# LED-zero35-SHIM.net
KiCad netlist of a schematic drawn in EAGLE
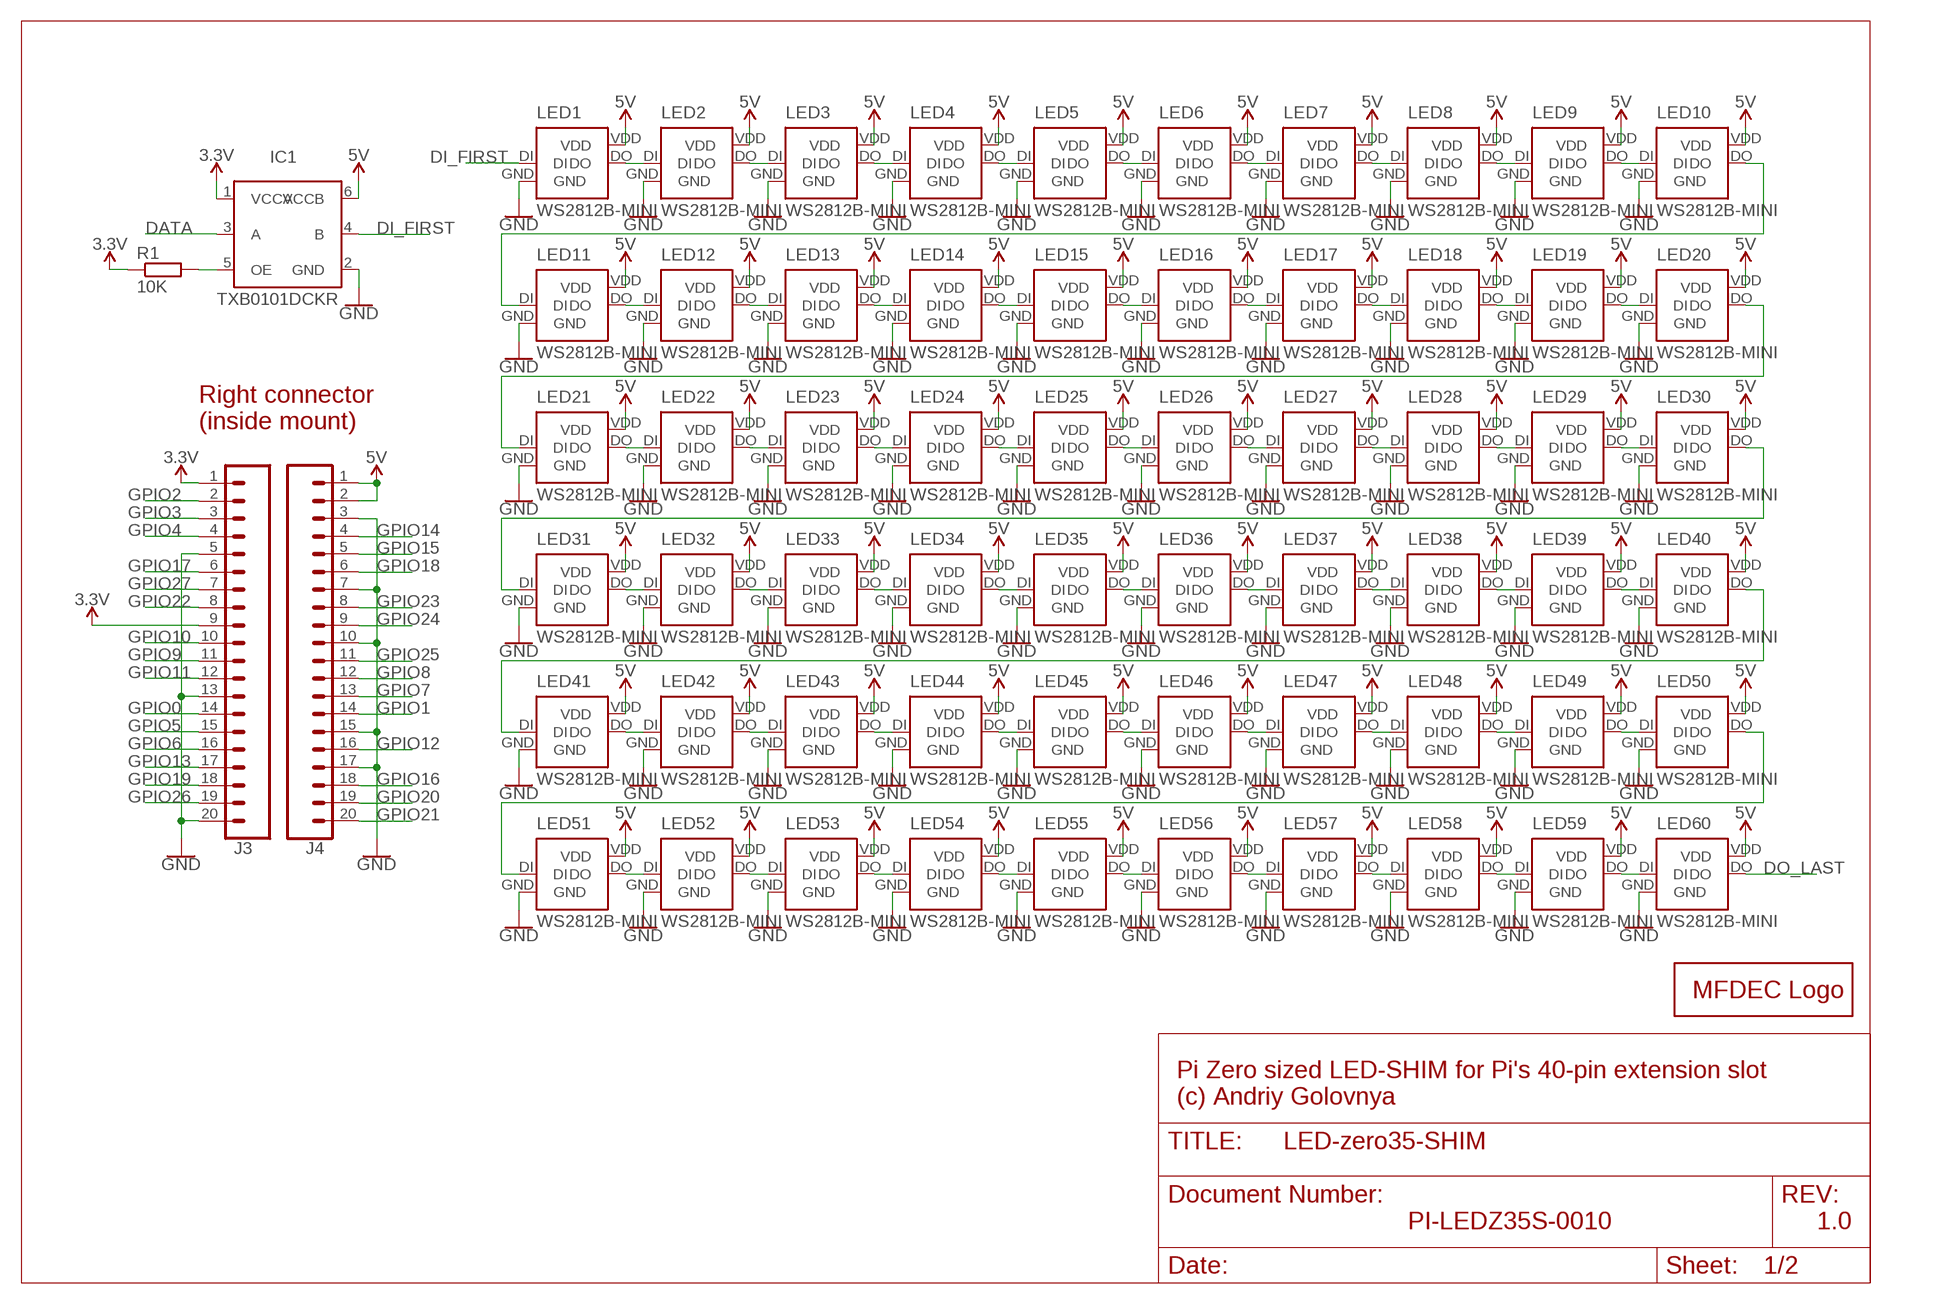
[diagram p0: schematic, sheet 1]
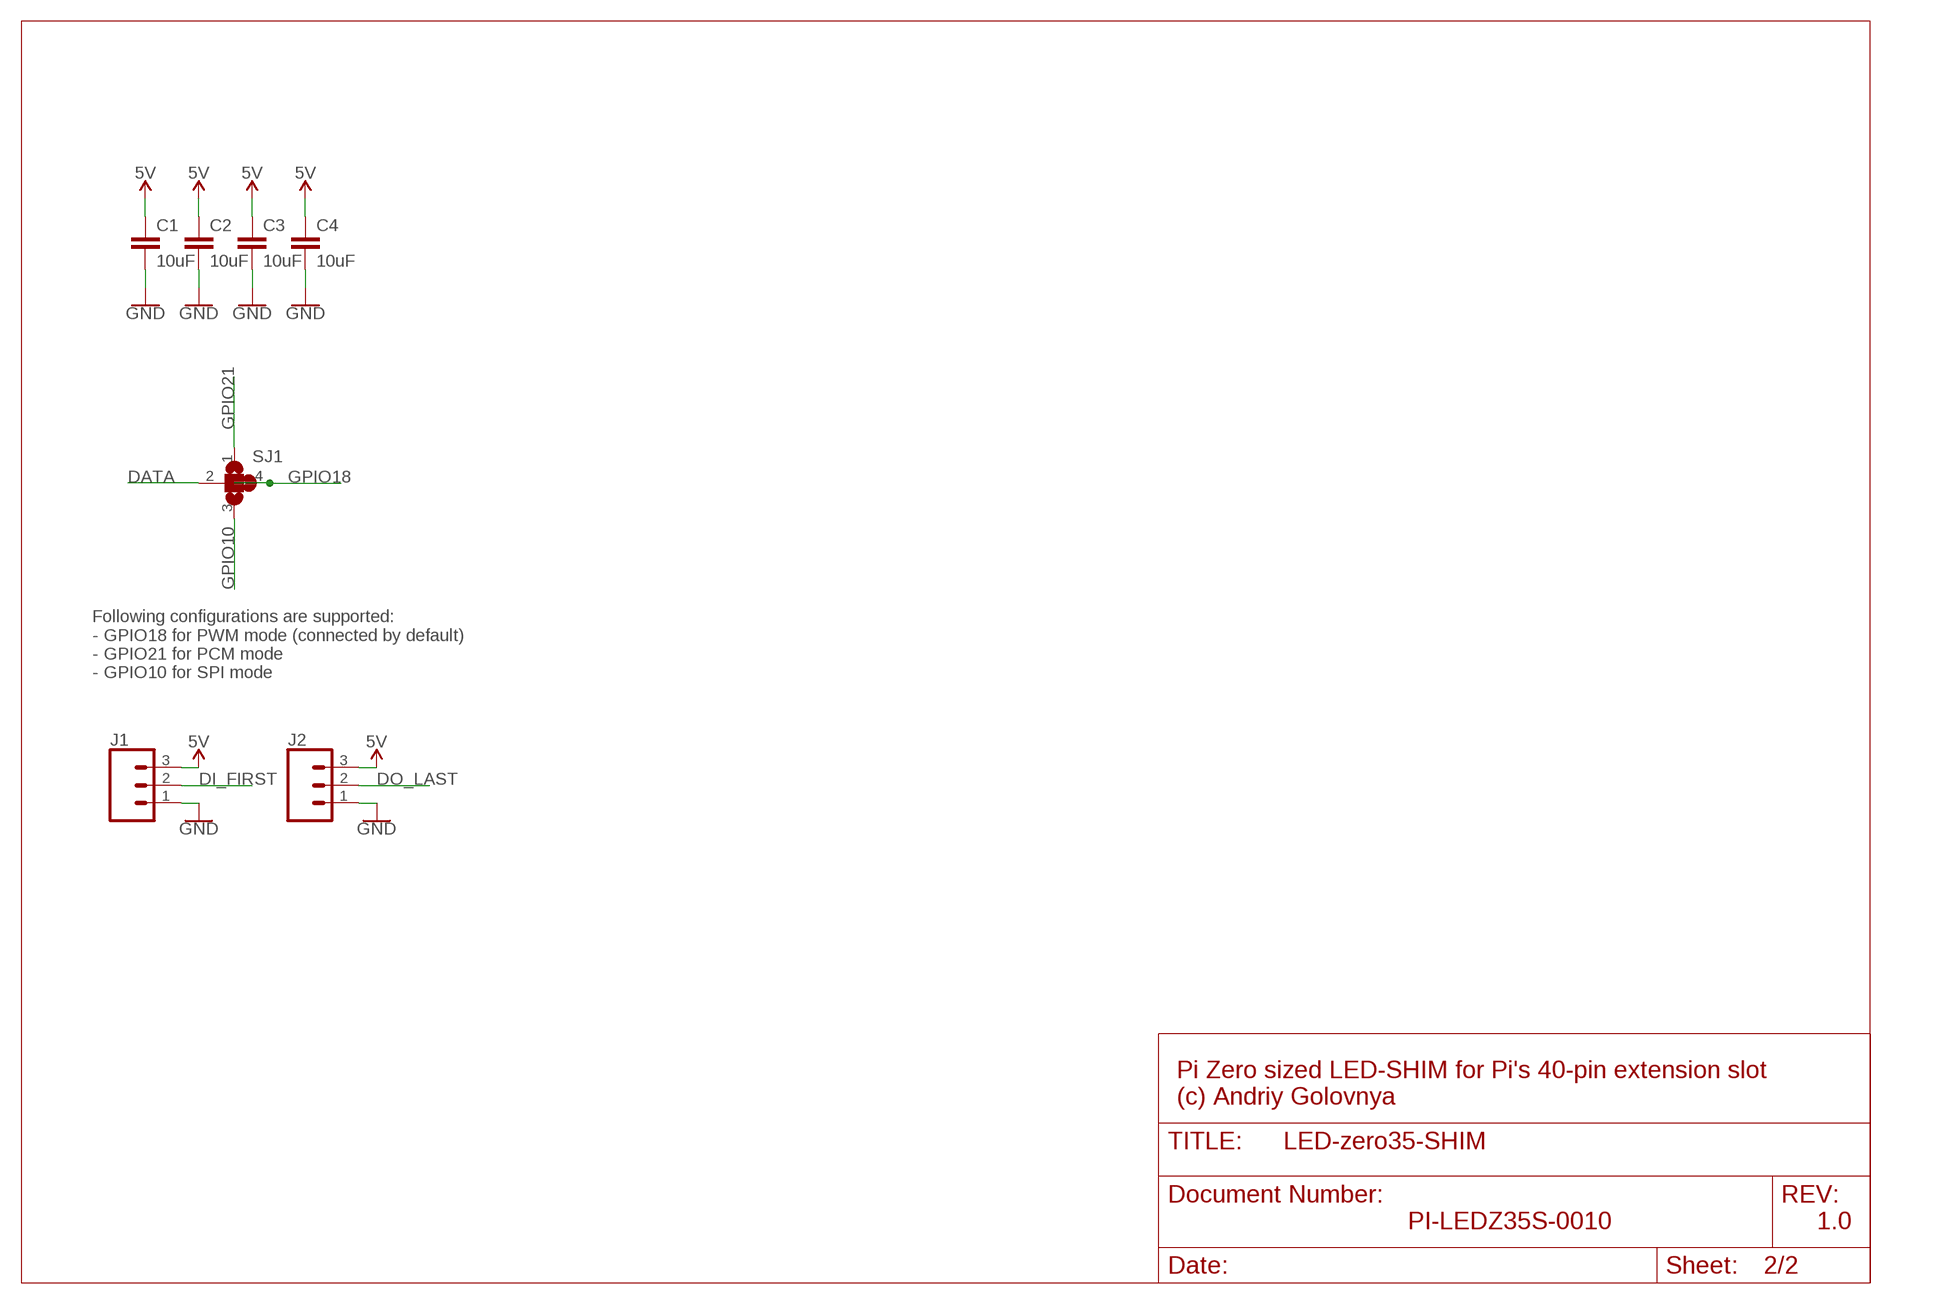
[diagram p1: schematic, sheet 2]

(export (version "E")
  (design (tool "Eeschema 10.0.6"))
  (components
    (comp (ref "IC1")
      (value "TXB0101DCKR")
      (footprint "eagle-import:SOT65P210X110-6N")
      (libsource (lib "eagle-import") (part "TXB0101DCKR"))
    )
    (comp (ref "J3")
      (value "CONN_20LOCK")
      (footprint "eagle-import:1X20_LOCK")
      (libsource (lib "eagle-import") (part "CONN_20LOCK"))
    )
    (comp (ref "J4")
      (value "CONN_20LOCK")
      (footprint "eagle-import:1X20_LOCK")
      (libsource (lib "eagle-import") (part "CONN_20LOCK"))
    )
    (comp (ref "LED1")
      (value "WS2812B-MINI")
      (footprint "eagle-import:WS2812X-MINI")
      (libsource (lib "eagle-import") (part "WS2812B-MINI"))
    )
    (comp (ref "LED2")
      (value "WS2812B-MINI")
      (footprint "eagle-import:WS2812X-MINI")
      (libsource (lib "eagle-import") (part "WS2812B-MINI"))
    )
    (comp (ref "LED3")
      (value "WS2812B-MINI")
      (footprint "eagle-import:WS2812X-MINI")
      (libsource (lib "eagle-import") (part "WS2812B-MINI"))
    )
    (comp (ref "LED4")
      (value "WS2812B-MINI")
      (footprint "eagle-import:WS2812X-MINI")
      (libsource (lib "eagle-import") (part "WS2812B-MINI"))
    )
    (comp (ref "LED5")
      (value "WS2812B-MINI")
      (footprint "eagle-import:WS2812X-MINI")
      (libsource (lib "eagle-import") (part "WS2812B-MINI"))
    )
    (comp (ref "LED6")
      (value "WS2812B-MINI")
      (footprint "eagle-import:WS2812X-MINI")
      (libsource (lib "eagle-import") (part "WS2812B-MINI"))
    )
    (comp (ref "LED7")
      (value "WS2812B-MINI")
      (footprint "eagle-import:WS2812X-MINI")
      (libsource (lib "eagle-import") (part "WS2812B-MINI"))
    )
    (comp (ref "LED8")
      (value "WS2812B-MINI")
      (footprint "eagle-import:WS2812X-MINI")
      (libsource (lib "eagle-import") (part "WS2812B-MINI"))
    )
    (comp (ref "LED9")
      (value "WS2812B-MINI")
      (footprint "eagle-import:WS2812X-MINI")
      (libsource (lib "eagle-import") (part "WS2812B-MINI"))
    )
    (comp (ref "LED10")
      (value "WS2812B-MINI")
      (footprint "eagle-import:WS2812X-MINI")
      (libsource (lib "eagle-import") (part "WS2812B-MINI"))
    )
    (comp (ref "LED11")
      (value "WS2812B-MINI")
      (footprint "eagle-import:WS2812X-MINI")
      (libsource (lib "eagle-import") (part "WS2812B-MINI"))
    )
    (comp (ref "LED12")
      (value "WS2812B-MINI")
      (footprint "eagle-import:WS2812X-MINI")
      (libsource (lib "eagle-import") (part "WS2812B-MINI"))
    )
    (comp (ref "LED13")
      (value "WS2812B-MINI")
      (footprint "eagle-import:WS2812X-MINI")
      (libsource (lib "eagle-import") (part "WS2812B-MINI"))
    )
    (comp (ref "LED14")
      (value "WS2812B-MINI")
      (footprint "eagle-import:WS2812X-MINI")
      (libsource (lib "eagle-import") (part "WS2812B-MINI"))
    )
    (comp (ref "LED15")
      (value "WS2812B-MINI")
      (footprint "eagle-import:WS2812X-MINI")
      (libsource (lib "eagle-import") (part "WS2812B-MINI"))
    )
    (comp (ref "LED16")
      (value "WS2812B-MINI")
      (footprint "eagle-import:WS2812X-MINI")
      (libsource (lib "eagle-import") (part "WS2812B-MINI"))
    )
    (comp (ref "LED17")
      (value "WS2812B-MINI")
      (footprint "eagle-import:WS2812X-MINI")
      (libsource (lib "eagle-import") (part "WS2812B-MINI"))
    )
    (comp (ref "LED18")
      (value "WS2812B-MINI")
      (footprint "eagle-import:WS2812X-MINI")
      (libsource (lib "eagle-import") (part "WS2812B-MINI"))
    )
    (comp (ref "LED19")
      (value "WS2812B-MINI")
      (footprint "eagle-import:WS2812X-MINI")
      (libsource (lib "eagle-import") (part "WS2812B-MINI"))
    )
    (comp (ref "LED20")
      (value "WS2812B-MINI")
      (footprint "eagle-import:WS2812X-MINI")
      (libsource (lib "eagle-import") (part "WS2812B-MINI"))
    )
    (comp (ref "LED21")
      (value "WS2812B-MINI")
      (footprint "eagle-import:WS2812X-MINI")
      (libsource (lib "eagle-import") (part "WS2812B-MINI"))
    )
    (comp (ref "LED22")
      (value "WS2812B-MINI")
      (footprint "eagle-import:WS2812X-MINI")
      (libsource (lib "eagle-import") (part "WS2812B-MINI"))
    )
    (comp (ref "LED23")
      (value "WS2812B-MINI")
      (footprint "eagle-import:WS2812X-MINI")
      (libsource (lib "eagle-import") (part "WS2812B-MINI"))
    )
    (comp (ref "LED24")
      (value "WS2812B-MINI")
      (footprint "eagle-import:WS2812X-MINI")
      (libsource (lib "eagle-import") (part "WS2812B-MINI"))
    )
    (comp (ref "LED25")
      (value "WS2812B-MINI")
      (footprint "eagle-import:WS2812X-MINI")
      (libsource (lib "eagle-import") (part "WS2812B-MINI"))
    )
    (comp (ref "LED26")
      (value "WS2812B-MINI")
      (footprint "eagle-import:WS2812X-MINI")
      (libsource (lib "eagle-import") (part "WS2812B-MINI"))
    )
    (comp (ref "LED27")
      (value "WS2812B-MINI")
      (footprint "eagle-import:WS2812X-MINI")
      (libsource (lib "eagle-import") (part "WS2812B-MINI"))
    )
    (comp (ref "LED28")
      (value "WS2812B-MINI")
      (footprint "eagle-import:WS2812X-MINI")
      (libsource (lib "eagle-import") (part "WS2812B-MINI"))
    )
    (comp (ref "LED29")
      (value "WS2812B-MINI")
      (footprint "eagle-import:WS2812X-MINI")
      (libsource (lib "eagle-import") (part "WS2812B-MINI"))
    )
    (comp (ref "LED30")
      (value "WS2812B-MINI")
      (footprint "eagle-import:WS2812X-MINI")
      (libsource (lib "eagle-import") (part "WS2812B-MINI"))
    )
    (comp (ref "LED31")
      (value "WS2812B-MINI")
      (footprint "eagle-import:WS2812X-MINI")
      (libsource (lib "eagle-import") (part "WS2812B-MINI"))
    )
    (comp (ref "LED32")
      (value "WS2812B-MINI")
      (footprint "eagle-import:WS2812X-MINI")
      (libsource (lib "eagle-import") (part "WS2812B-MINI"))
    )
    (comp (ref "LED33")
      (value "WS2812B-MINI")
      (footprint "eagle-import:WS2812X-MINI")
      (libsource (lib "eagle-import") (part "WS2812B-MINI"))
    )
    (comp (ref "LED34")
      (value "WS2812B-MINI")
      (footprint "eagle-import:WS2812X-MINI")
      (libsource (lib "eagle-import") (part "WS2812B-MINI"))
    )
    (comp (ref "LED35")
      (value "WS2812B-MINI")
      (footprint "eagle-import:WS2812X-MINI")
      (libsource (lib "eagle-import") (part "WS2812B-MINI"))
    )
    (comp (ref "LED36")
      (value "WS2812B-MINI")
      (footprint "eagle-import:WS2812X-MINI")
      (libsource (lib "eagle-import") (part "WS2812B-MINI"))
    )
    (comp (ref "LED37")
      (value "WS2812B-MINI")
      (footprint "eagle-import:WS2812X-MINI")
      (libsource (lib "eagle-import") (part "WS2812B-MINI"))
    )
    (comp (ref "LED38")
      (value "WS2812B-MINI")
      (footprint "eagle-import:WS2812X-MINI")
      (libsource (lib "eagle-import") (part "WS2812B-MINI"))
    )
    (comp (ref "LED39")
      (value "WS2812B-MINI")
      (footprint "eagle-import:WS2812X-MINI")
      (libsource (lib "eagle-import") (part "WS2812B-MINI"))
    )
    (comp (ref "LED40")
      (value "WS2812B-MINI")
      (footprint "eagle-import:WS2812X-MINI")
      (libsource (lib "eagle-import") (part "WS2812B-MINI"))
    )
    (comp (ref "LED41")
      (value "WS2812B-MINI")
      (footprint "eagle-import:WS2812X-MINI")
      (libsource (lib "eagle-import") (part "WS2812B-MINI"))
    )
    (comp (ref "LED42")
      (value "WS2812B-MINI")
      (footprint "eagle-import:WS2812X-MINI")
      (libsource (lib "eagle-import") (part "WS2812B-MINI"))
    )
    (comp (ref "LED43")
      (value "WS2812B-MINI")
      (footprint "eagle-import:WS2812X-MINI")
      (libsource (lib "eagle-import") (part "WS2812B-MINI"))
    )
    (comp (ref "LED44")
      (value "WS2812B-MINI")
      (footprint "eagle-import:WS2812X-MINI")
      (libsource (lib "eagle-import") (part "WS2812B-MINI"))
    )
    (comp (ref "LED45")
      (value "WS2812B-MINI")
      (footprint "eagle-import:WS2812X-MINI")
      (libsource (lib "eagle-import") (part "WS2812B-MINI"))
    )
    (comp (ref "LED46")
      (value "WS2812B-MINI")
      (footprint "eagle-import:WS2812X-MINI")
      (libsource (lib "eagle-import") (part "WS2812B-MINI"))
    )
    (comp (ref "LED47")
      (value "WS2812B-MINI")
      (footprint "eagle-import:WS2812X-MINI")
      (libsource (lib "eagle-import") (part "WS2812B-MINI"))
    )
    (comp (ref "LED48")
      (value "WS2812B-MINI")
      (footprint "eagle-import:WS2812X-MINI")
      (libsource (lib "eagle-import") (part "WS2812B-MINI"))
    )
    (comp (ref "LED49")
      (value "WS2812B-MINI")
      (footprint "eagle-import:WS2812X-MINI")
      (libsource (lib "eagle-import") (part "WS2812B-MINI"))
    )
    (comp (ref "LED50")
      (value "WS2812B-MINI")
      (footprint "eagle-import:WS2812X-MINI")
      (libsource (lib "eagle-import") (part "WS2812B-MINI"))
    )
    (comp (ref "LED51")
      (value "WS2812B-MINI")
      (footprint "eagle-import:WS2812X-MINI")
      (libsource (lib "eagle-import") (part "WS2812B-MINI"))
    )
    (comp (ref "LED52")
      (value "WS2812B-MINI")
      (footprint "eagle-import:WS2812X-MINI")
      (libsource (lib "eagle-import") (part "WS2812B-MINI"))
    )
    (comp (ref "LED53")
      (value "WS2812B-MINI")
      (footprint "eagle-import:WS2812X-MINI")
      (libsource (lib "eagle-import") (part "WS2812B-MINI"))
    )
    (comp (ref "LED54")
      (value "WS2812B-MINI")
      (footprint "eagle-import:WS2812X-MINI")
      (libsource (lib "eagle-import") (part "WS2812B-MINI"))
    )
    (comp (ref "LED55")
      (value "WS2812B-MINI")
      (footprint "eagle-import:WS2812X-MINI")
      (libsource (lib "eagle-import") (part "WS2812B-MINI"))
    )
    (comp (ref "LED56")
      (value "WS2812B-MINI")
      (footprint "eagle-import:WS2812X-MINI")
      (libsource (lib "eagle-import") (part "WS2812B-MINI"))
    )
    (comp (ref "LED57")
      (value "WS2812B-MINI")
      (footprint "eagle-import:WS2812X-MINI")
      (libsource (lib "eagle-import") (part "WS2812B-MINI"))
    )
    (comp (ref "LED58")
      (value "WS2812B-MINI")
      (footprint "eagle-import:WS2812X-MINI")
      (libsource (lib "eagle-import") (part "WS2812B-MINI"))
    )
    (comp (ref "LED59")
      (value "WS2812B-MINI")
      (footprint "eagle-import:WS2812X-MINI")
      (libsource (lib "eagle-import") (part "WS2812B-MINI"))
    )
    (comp (ref "LED60")
      (value "WS2812B-MINI")
      (footprint "eagle-import:WS2812X-MINI")
      (libsource (lib "eagle-import") (part "WS2812B-MINI"))
    )
    (comp (ref "LOGO1")
      (value "MFDECLOGO_L_30MM")
      (footprint "eagle-import:MFDEC_L_30MM")
      (libsource (lib "eagle-import") (part "MFDECLOGO_L_30MM"))
    )
    (comp (ref "R1")
      (value "10K")
      (footprint "eagle-import:R0402")
      (libsource (lib "eagle-import") (part "R-EU_R0402"))
    )
    (comp (ref "C1")
      (value "10uF")
      (footprint "eagle-import:C0805")
      (libsource (lib "eagle-import") (part "C-EUC0805"))
    )
    (comp (ref "C2")
      (value "10uF")
      (footprint "eagle-import:C0805")
      (libsource (lib "eagle-import") (part "C-EUC0805"))
    )
    (comp (ref "C3")
      (value "10uF")
      (footprint "eagle-import:C0805")
      (libsource (lib "eagle-import") (part "C-EUC0805"))
    )
    (comp (ref "C4")
      (value "10uF")
      (footprint "eagle-import:C0805")
      (libsource (lib "eagle-import") (part "C-EUC0805"))
    )
    (comp (ref "J1")
      (value "CONN_03")
      (footprint "eagle-import:1X03")
      (libsource (lib "eagle-import") (part "CONN_03"))
    )
    (comp (ref "J2")
      (value "CONN_03")
      (footprint "eagle-import:1X03")
      (libsource (lib "eagle-import") (part "CONN_03"))
    )
    (comp (ref "SJ1")
      (value "SJ3")
      (footprint "eagle-import:SJ_3")
      (libsource (lib "eagle-import") (part "SJ3"))
    )
  )
  (nets
    (net (code "1") (name "3.3V") (class "Default")
      (node (ref "IC1") (pin "1") (pinfunction "VCCA_1") (pintype "power_in"))
      (node (ref "J3") (pin "1") (pinfunction "1_1") (pintype "passive"))
      (node (ref "J3") (pin "9") (pinfunction "9_9") (pintype "passive"))
      (node (ref "R1") (pin "1") (pinfunction "1_1") (pintype "passive"))
    )
    (net (code "2") (name "5V") (class "Default")
      (node (ref "C1") (pin "1") (pinfunction "1_1") (pintype "passive"))
      (node (ref "C2") (pin "1") (pinfunction "1_1") (pintype "passive"))
      (node (ref "C3") (pin "1") (pinfunction "1_1") (pintype "passive"))
      (node (ref "C4") (pin "1") (pinfunction "1_1") (pintype "passive"))
      (node (ref "IC1") (pin "6") (pinfunction "VCCB_6") (pintype "power_in"))
      (node (ref "J1") (pin "3") (pinfunction "3_3") (pintype "passive"))
      (node (ref "J2") (pin "3") (pinfunction "3_3") (pintype "passive"))
      (node (ref "J4") (pin "1") (pinfunction "1_1") (pintype "passive"))
      (node (ref "J4") (pin "2") (pinfunction "2_2") (pintype "passive"))
      (node (ref "LED1") (pin "VDD") (pinfunction "VDD_VDD") (pintype "power_in"))
      (node (ref "LED10") (pin "VDD") (pinfunction "VDD_VDD") (pintype "power_in"))
      (node (ref "LED11") (pin "VDD") (pinfunction "VDD_VDD") (pintype "power_in"))
      (node (ref "LED12") (pin "VDD") (pinfunction "VDD_VDD") (pintype "power_in"))
      (node (ref "LED13") (pin "VDD") (pinfunction "VDD_VDD") (pintype "power_in"))
      (node (ref "LED14") (pin "VDD") (pinfunction "VDD_VDD") (pintype "power_in"))
      (node (ref "LED15") (pin "VDD") (pinfunction "VDD_VDD") (pintype "power_in"))
      (node (ref "LED16") (pin "VDD") (pinfunction "VDD_VDD") (pintype "power_in"))
      (node (ref "LED17") (pin "VDD") (pinfunction "VDD_VDD") (pintype "power_in"))
      (node (ref "LED18") (pin "VDD") (pinfunction "VDD_VDD") (pintype "power_in"))
      (node (ref "LED19") (pin "VDD") (pinfunction "VDD_VDD") (pintype "power_in"))
      (node (ref "LED2") (pin "VDD") (pinfunction "VDD_VDD") (pintype "power_in"))
      (node (ref "LED20") (pin "VDD") (pinfunction "VDD_VDD") (pintype "power_in"))
      (node (ref "LED21") (pin "VDD") (pinfunction "VDD_VDD") (pintype "power_in"))
      (node (ref "LED22") (pin "VDD") (pinfunction "VDD_VDD") (pintype "power_in"))
      (node (ref "LED23") (pin "VDD") (pinfunction "VDD_VDD") (pintype "power_in"))
      (node (ref "LED24") (pin "VDD") (pinfunction "VDD_VDD") (pintype "power_in"))
      (node (ref "LED25") (pin "VDD") (pinfunction "VDD_VDD") (pintype "power_in"))
      (node (ref "LED26") (pin "VDD") (pinfunction "VDD_VDD") (pintype "power_in"))
      (node (ref "LED27") (pin "VDD") (pinfunction "VDD_VDD") (pintype "power_in"))
      (node (ref "LED28") (pin "VDD") (pinfunction "VDD_VDD") (pintype "power_in"))
      (node (ref "LED29") (pin "VDD") (pinfunction "VDD_VDD") (pintype "power_in"))
      (node (ref "LED3") (pin "VDD") (pinfunction "VDD_VDD") (pintype "power_in"))
      (node (ref "LED30") (pin "VDD") (pinfunction "VDD_VDD") (pintype "power_in"))
      (node (ref "LED31") (pin "VDD") (pinfunction "VDD_VDD") (pintype "power_in"))
      (node (ref "LED32") (pin "VDD") (pinfunction "VDD_VDD") (pintype "power_in"))
      (node (ref "LED33") (pin "VDD") (pinfunction "VDD_VDD") (pintype "power_in"))
      (node (ref "LED34") (pin "VDD") (pinfunction "VDD_VDD") (pintype "power_in"))
      (node (ref "LED35") (pin "VDD") (pinfunction "VDD_VDD") (pintype "power_in"))
      (node (ref "LED36") (pin "VDD") (pinfunction "VDD_VDD") (pintype "power_in"))
      (node (ref "LED37") (pin "VDD") (pinfunction "VDD_VDD") (pintype "power_in"))
      (node (ref "LED38") (pin "VDD") (pinfunction "VDD_VDD") (pintype "power_in"))
      (node (ref "LED39") (pin "VDD") (pinfunction "VDD_VDD") (pintype "power_in"))
      (node (ref "LED4") (pin "VDD") (pinfunction "VDD_VDD") (pintype "power_in"))
      (node (ref "LED40") (pin "VDD") (pinfunction "VDD_VDD") (pintype "power_in"))
      (node (ref "LED41") (pin "VDD") (pinfunction "VDD_VDD") (pintype "power_in"))
      (node (ref "LED42") (pin "VDD") (pinfunction "VDD_VDD") (pintype "power_in"))
      (node (ref "LED43") (pin "VDD") (pinfunction "VDD_VDD") (pintype "power_in"))
      (node (ref "LED44") (pin "VDD") (pinfunction "VDD_VDD") (pintype "power_in"))
      (node (ref "LED45") (pin "VDD") (pinfunction "VDD_VDD") (pintype "power_in"))
      (node (ref "LED46") (pin "VDD") (pinfunction "VDD_VDD") (pintype "power_in"))
      (node (ref "LED47") (pin "VDD") (pinfunction "VDD_VDD") (pintype "power_in"))
      (node (ref "LED48") (pin "VDD") (pinfunction "VDD_VDD") (pintype "power_in"))
      (node (ref "LED49") (pin "VDD") (pinfunction "VDD_VDD") (pintype "power_in"))
      (node (ref "LED5") (pin "VDD") (pinfunction "VDD_VDD") (pintype "power_in"))
      (node (ref "LED50") (pin "VDD") (pinfunction "VDD_VDD") (pintype "power_in"))
      (node (ref "LED51") (pin "VDD") (pinfunction "VDD_VDD") (pintype "power_in"))
      (node (ref "LED52") (pin "VDD") (pinfunction "VDD_VDD") (pintype "power_in"))
      (node (ref "LED53") (pin "VDD") (pinfunction "VDD_VDD") (pintype "power_in"))
      (node (ref "LED54") (pin "VDD") (pinfunction "VDD_VDD") (pintype "power_in"))
      (node (ref "LED55") (pin "VDD") (pinfunction "VDD_VDD") (pintype "power_in"))
      (node (ref "LED56") (pin "VDD") (pinfunction "VDD_VDD") (pintype "power_in"))
      (node (ref "LED57") (pin "VDD") (pinfunction "VDD_VDD") (pintype "power_in"))
      (node (ref "LED58") (pin "VDD") (pinfunction "VDD_VDD") (pintype "power_in"))
      (node (ref "LED59") (pin "VDD") (pinfunction "VDD_VDD") (pintype "power_in"))
      (node (ref "LED6") (pin "VDD") (pinfunction "VDD_VDD") (pintype "power_in"))
      (node (ref "LED60") (pin "VDD") (pinfunction "VDD_VDD") (pintype "power_in"))
      (node (ref "LED7") (pin "VDD") (pinfunction "VDD_VDD") (pintype "power_in"))
      (node (ref "LED8") (pin "VDD") (pinfunction "VDD_VDD") (pintype "power_in"))
      (node (ref "LED9") (pin "VDD") (pinfunction "VDD_VDD") (pintype "power_in"))
    )
    (net (code "3") (name "DATA") (class "Default")
      (node (ref "IC1") (pin "3") (pinfunction "A_3") (pintype "bidirectional"))
      (node (ref "SJ1") (pin "2") (pinfunction "2_2") (pintype "passive"))
    )
    (net (code "4") (name "DI_FIRST") (class "Default")
      (node (ref "IC1") (pin "4") (pinfunction "B_4") (pintype "bidirectional"))
      (node (ref "J1") (pin "2") (pinfunction "2_2") (pintype "passive"))
      (node (ref "LED1") (pin "DI") (pinfunction "DI_DI") (pintype "input"))
    )
    (net (code "5") (name "DO_LAST") (class "Default")
      (node (ref "J2") (pin "2") (pinfunction "2_2") (pintype "passive"))
      (node (ref "LED60") (pin "DO") (pinfunction "DO_DO") (pintype "output"))
    )
    (net (code "6") (name "GND") (class "Default")
      (node (ref "C1") (pin "2") (pinfunction "2_2") (pintype "passive"))
      (node (ref "C2") (pin "2") (pinfunction "2_2") (pintype "passive"))
      (node (ref "C3") (pin "2") (pinfunction "2_2") (pintype "passive"))
      (node (ref "C4") (pin "2") (pinfunction "2_2") (pintype "passive"))
      (node (ref "IC1") (pin "2") (pinfunction "GND_2") (pintype "power_in"))
      (node (ref "J1") (pin "1") (pinfunction "1_1") (pintype "passive"))
      (node (ref "J2") (pin "1") (pinfunction "1_1") (pintype "passive"))
      (node (ref "J3") (pin "13") (pinfunction "13_13") (pintype "passive"))
      (node (ref "J3") (pin "20") (pinfunction "20_20") (pintype "passive"))
      (node (ref "J3") (pin "5") (pinfunction "5_5") (pintype "passive"))
      (node (ref "J4") (pin "10") (pinfunction "10_10") (pintype "passive"))
      (node (ref "J4") (pin "15") (pinfunction "15_15") (pintype "passive"))
      (node (ref "J4") (pin "17") (pinfunction "17_17") (pintype "passive"))
      (node (ref "J4") (pin "3") (pinfunction "3_3") (pintype "passive"))
      (node (ref "J4") (pin "7") (pinfunction "7_7") (pintype "passive"))
      (node (ref "LED1") (pin "GND") (pinfunction "GND_GND") (pintype "power_in"))
      (node (ref "LED10") (pin "GND") (pinfunction "GND_GND") (pintype "power_in"))
      (node (ref "LED11") (pin "GND") (pinfunction "GND_GND") (pintype "power_in"))
      (node (ref "LED12") (pin "GND") (pinfunction "GND_GND") (pintype "power_in"))
      (node (ref "LED13") (pin "GND") (pinfunction "GND_GND") (pintype "power_in"))
      (node (ref "LED14") (pin "GND") (pinfunction "GND_GND") (pintype "power_in"))
      (node (ref "LED15") (pin "GND") (pinfunction "GND_GND") (pintype "power_in"))
      (node (ref "LED16") (pin "GND") (pinfunction "GND_GND") (pintype "power_in"))
      (node (ref "LED17") (pin "GND") (pinfunction "GND_GND") (pintype "power_in"))
      (node (ref "LED18") (pin "GND") (pinfunction "GND_GND") (pintype "power_in"))
      (node (ref "LED19") (pin "GND") (pinfunction "GND_GND") (pintype "power_in"))
      (node (ref "LED2") (pin "GND") (pinfunction "GND_GND") (pintype "power_in"))
      (node (ref "LED20") (pin "GND") (pinfunction "GND_GND") (pintype "power_in"))
      (node (ref "LED21") (pin "GND") (pinfunction "GND_GND") (pintype "power_in"))
      (node (ref "LED22") (pin "GND") (pinfunction "GND_GND") (pintype "power_in"))
      (node (ref "LED23") (pin "GND") (pinfunction "GND_GND") (pintype "power_in"))
      (node (ref "LED24") (pin "GND") (pinfunction "GND_GND") (pintype "power_in"))
      (node (ref "LED25") (pin "GND") (pinfunction "GND_GND") (pintype "power_in"))
      (node (ref "LED26") (pin "GND") (pinfunction "GND_GND") (pintype "power_in"))
      (node (ref "LED27") (pin "GND") (pinfunction "GND_GND") (pintype "power_in"))
      (node (ref "LED28") (pin "GND") (pinfunction "GND_GND") (pintype "power_in"))
      (node (ref "LED29") (pin "GND") (pinfunction "GND_GND") (pintype "power_in"))
      (node (ref "LED3") (pin "GND") (pinfunction "GND_GND") (pintype "power_in"))
      (node (ref "LED30") (pin "GND") (pinfunction "GND_GND") (pintype "power_in"))
      (node (ref "LED31") (pin "GND") (pinfunction "GND_GND") (pintype "power_in"))
      (node (ref "LED32") (pin "GND") (pinfunction "GND_GND") (pintype "power_in"))
      (node (ref "LED33") (pin "GND") (pinfunction "GND_GND") (pintype "power_in"))
      (node (ref "LED34") (pin "GND") (pinfunction "GND_GND") (pintype "power_in"))
      (node (ref "LED35") (pin "GND") (pinfunction "GND_GND") (pintype "power_in"))
      (node (ref "LED36") (pin "GND") (pinfunction "GND_GND") (pintype "power_in"))
      (node (ref "LED37") (pin "GND") (pinfunction "GND_GND") (pintype "power_in"))
      (node (ref "LED38") (pin "GND") (pinfunction "GND_GND") (pintype "power_in"))
      (node (ref "LED39") (pin "GND") (pinfunction "GND_GND") (pintype "power_in"))
      (node (ref "LED4") (pin "GND") (pinfunction "GND_GND") (pintype "power_in"))
      (node (ref "LED40") (pin "GND") (pinfunction "GND_GND") (pintype "power_in"))
      (node (ref "LED41") (pin "GND") (pinfunction "GND_GND") (pintype "power_in"))
      (node (ref "LED42") (pin "GND") (pinfunction "GND_GND") (pintype "power_in"))
      (node (ref "LED43") (pin "GND") (pinfunction "GND_GND") (pintype "power_in"))
      (node (ref "LED44") (pin "GND") (pinfunction "GND_GND") (pintype "power_in"))
      (node (ref "LED45") (pin "GND") (pinfunction "GND_GND") (pintype "power_in"))
      (node (ref "LED46") (pin "GND") (pinfunction "GND_GND") (pintype "power_in"))
      (node (ref "LED47") (pin "GND") (pinfunction "GND_GND") (pintype "power_in"))
      (node (ref "LED48") (pin "GND") (pinfunction "GND_GND") (pintype "power_in"))
      (node (ref "LED49") (pin "GND") (pinfunction "GND_GND") (pintype "power_in"))
      (node (ref "LED5") (pin "GND") (pinfunction "GND_GND") (pintype "power_in"))
      (node (ref "LED50") (pin "GND") (pinfunction "GND_GND") (pintype "power_in"))
      (node (ref "LED51") (pin "GND") (pinfunction "GND_GND") (pintype "power_in"))
      (node (ref "LED52") (pin "GND") (pinfunction "GND_GND") (pintype "power_in"))
      (node (ref "LED53") (pin "GND") (pinfunction "GND_GND") (pintype "power_in"))
      (node (ref "LED54") (pin "GND") (pinfunction "GND_GND") (pintype "power_in"))
      (node (ref "LED55") (pin "GND") (pinfunction "GND_GND") (pintype "power_in"))
      (node (ref "LED56") (pin "GND") (pinfunction "GND_GND") (pintype "power_in"))
      (node (ref "LED57") (pin "GND") (pinfunction "GND_GND") (pintype "power_in"))
      (node (ref "LED58") (pin "GND") (pinfunction "GND_GND") (pintype "power_in"))
      (node (ref "LED59") (pin "GND") (pinfunction "GND_GND") (pintype "power_in"))
      (node (ref "LED6") (pin "GND") (pinfunction "GND_GND") (pintype "power_in"))
      (node (ref "LED60") (pin "GND") (pinfunction "GND_GND") (pintype "power_in"))
      (node (ref "LED7") (pin "GND") (pinfunction "GND_GND") (pintype "power_in"))
      (node (ref "LED8") (pin "GND") (pinfunction "GND_GND") (pintype "power_in"))
      (node (ref "LED9") (pin "GND") (pinfunction "GND_GND") (pintype "power_in"))
    )
    (net (code "7") (name "GPIO0") (class "Default")
      (node (ref "J3") (pin "14") (pinfunction "14_14") (pintype "passive"))
    )
    (net (code "8") (name "GPIO1") (class "Default")
      (node (ref "J4") (pin "14") (pinfunction "14_14") (pintype "passive"))
    )
    (net (code "9") (name "GPIO2") (class "Default")
      (node (ref "J3") (pin "2") (pinfunction "2_2") (pintype "passive"))
    )
    (net (code "10") (name "GPIO3") (class "Default")
      (node (ref "J3") (pin "3") (pinfunction "3_3") (pintype "passive"))
    )
    (net (code "11") (name "GPIO4") (class "Default")
      (node (ref "J3") (pin "4") (pinfunction "4_4") (pintype "passive"))
    )
    (net (code "12") (name "GPIO5") (class "Default")
      (node (ref "J3") (pin "15") (pinfunction "15_15") (pintype "passive"))
    )
    (net (code "13") (name "GPIO6") (class "Default")
      (node (ref "J3") (pin "16") (pinfunction "16_16") (pintype "passive"))
    )
    (net (code "14") (name "GPIO7") (class "Default")
      (node (ref "J4") (pin "13") (pinfunction "13_13") (pintype "passive"))
    )
    (net (code "15") (name "GPIO8") (class "Default")
      (node (ref "J4") (pin "12") (pinfunction "12_12") (pintype "passive"))
    )
    (net (code "16") (name "GPIO9") (class "Default")
      (node (ref "J3") (pin "11") (pinfunction "11_11") (pintype "passive"))
    )
    (net (code "17") (name "GPIO10") (class "Default")
      (node (ref "J3") (pin "10") (pinfunction "10_10") (pintype "passive"))
      (node (ref "SJ1") (pin "3") (pinfunction "3_3") (pintype "passive"))
    )
    (net (code "18") (name "GPIO11") (class "Default")
      (node (ref "J3") (pin "12") (pinfunction "12_12") (pintype "passive"))
    )
    (net (code "19") (name "GPIO12") (class "Default")
      (node (ref "J4") (pin "16") (pinfunction "16_16") (pintype "passive"))
    )
    (net (code "20") (name "GPIO13") (class "Default")
      (node (ref "J3") (pin "17") (pinfunction "17_17") (pintype "passive"))
    )
    (net (code "21") (name "GPIO14") (class "Default")
      (node (ref "J4") (pin "4") (pinfunction "4_4") (pintype "passive"))
    )
    (net (code "22") (name "GPIO15") (class "Default")
      (node (ref "J4") (pin "5") (pinfunction "5_5") (pintype "passive"))
    )
    (net (code "23") (name "GPIO16") (class "Default")
      (node (ref "J4") (pin "18") (pinfunction "18_18") (pintype "passive"))
    )
    (net (code "24") (name "GPIO17") (class "Default")
      (node (ref "J3") (pin "6") (pinfunction "6_6") (pintype "passive"))
    )
    (net (code "25") (name "GPIO18") (class "Default")
      (node (ref "J4") (pin "6") (pinfunction "6_6") (pintype "passive"))
      (node (ref "SJ1") (pin "4") (pinfunction "4_4") (pintype "passive"))
    )
    (net (code "26") (name "GPIO19") (class "Default")
      (node (ref "J3") (pin "18") (pinfunction "18_18") (pintype "passive"))
    )
    (net (code "27") (name "GPIO20") (class "Default")
      (node (ref "J4") (pin "19") (pinfunction "19_19") (pintype "passive"))
    )
    (net (code "28") (name "GPIO21") (class "Default")
      (node (ref "J4") (pin "20") (pinfunction "20_20") (pintype "passive"))
      (node (ref "SJ1") (pin "1") (pinfunction "1_1") (pintype "passive"))
    )
    (net (code "29") (name "GPIO22") (class "Default")
      (node (ref "J3") (pin "8") (pinfunction "8_8") (pintype "passive"))
    )
    (net (code "30") (name "GPIO23") (class "Default")
      (node (ref "J4") (pin "8") (pinfunction "8_8") (pintype "passive"))
    )
    (net (code "31") (name "GPIO24") (class "Default")
      (node (ref "J4") (pin "9") (pinfunction "9_9") (pintype "passive"))
    )
    (net (code "32") (name "GPIO25") (class "Default")
      (node (ref "J4") (pin "11") (pinfunction "11_11") (pintype "passive"))
    )
    (net (code "33") (name "GPIO26") (class "Default")
      (node (ref "J3") (pin "19") (pinfunction "19_19") (pintype "passive"))
    )
    (net (code "34") (name "GPIO27") (class "Default")
      (node (ref "J3") (pin "7") (pinfunction "7_7") (pintype "passive"))
    )
    (net (code "35") (name "Net-(IC1-OE)") (class "Default")
      (node (ref "IC1") (pin "5") (pinfunction "OE_5") (pintype "input"))
      (node (ref "R1") (pin "2") (pinfunction "2_2") (pintype "passive"))
    )
    (net (code "36") (name "Net-(LED1-PadDO)") (class "Default")
      (node (ref "LED1") (pin "DO") (pinfunction "DO_DO") (pintype "output"))
      (node (ref "LED2") (pin "DI") (pinfunction "DI_DI") (pintype "input"))
    )
    (net (code "37") (name "Net-(LED2-PadDO)") (class "Default")
      (node (ref "LED2") (pin "DO") (pinfunction "DO_DO") (pintype "output"))
      (node (ref "LED3") (pin "DI") (pinfunction "DI_DI") (pintype "input"))
    )
    (net (code "38") (name "Net-(LED3-PadDO)") (class "Default")
      (node (ref "LED3") (pin "DO") (pinfunction "DO_DO") (pintype "output"))
      (node (ref "LED4") (pin "DI") (pinfunction "DI_DI") (pintype "input"))
    )
    (net (code "39") (name "Net-(LED4-PadDO)") (class "Default")
      (node (ref "LED4") (pin "DO") (pinfunction "DO_DO") (pintype "output"))
      (node (ref "LED5") (pin "DI") (pinfunction "DI_DI") (pintype "input"))
    )
    (net (code "40") (name "Net-(LED5-PadDO)") (class "Default")
      (node (ref "LED5") (pin "DO") (pinfunction "DO_DO") (pintype "output"))
      (node (ref "LED6") (pin "DI") (pinfunction "DI_DI") (pintype "input"))
    )
    (net (code "41") (name "Net-(LED6-PadDO)") (class "Default")
      (node (ref "LED6") (pin "DO") (pinfunction "DO_DO") (pintype "output"))
      (node (ref "LED7") (pin "DI") (pinfunction "DI_DI") (pintype "input"))
    )
    (net (code "42") (name "Net-(LED7-PadDO)") (class "Default")
      (node (ref "LED7") (pin "DO") (pinfunction "DO_DO") (pintype "output"))
      (node (ref "LED8") (pin "DI") (pinfunction "DI_DI") (pintype "input"))
    )
    (net (code "43") (name "Net-(LED8-PadDO)") (class "Default")
      (node (ref "LED8") (pin "DO") (pinfunction "DO_DO") (pintype "output"))
      (node (ref "LED9") (pin "DI") (pinfunction "DI_DI") (pintype "input"))
    )
    (net (code "44") (name "Net-(LED10-PadDI)") (class "Default")
      (node (ref "LED10") (pin "DI") (pinfunction "DI_DI") (pintype "input"))
      (node (ref "LED9") (pin "DO") (pinfunction "DO_DO") (pintype "output"))
    )
    (net (code "45") (name "Net-(LED10-PadDO)") (class "Default")
      (node (ref "LED10") (pin "DO") (pinfunction "DO_DO") (pintype "output"))
      (node (ref "LED11") (pin "DI") (pinfunction "DI_DI") (pintype "input"))
    )
    (net (code "46") (name "Net-(LED11-PadDO)") (class "Default")
      (node (ref "LED11") (pin "DO") (pinfunction "DO_DO") (pintype "output"))
      (node (ref "LED12") (pin "DI") (pinfunction "DI_DI") (pintype "input"))
    )
    (net (code "47") (name "Net-(LED12-PadDO)") (class "Default")
      (node (ref "LED12") (pin "DO") (pinfunction "DO_DO") (pintype "output"))
      (node (ref "LED13") (pin "DI") (pinfunction "DI_DI") (pintype "input"))
    )
    (net (code "48") (name "Net-(LED13-PadDO)") (class "Default")
      (node (ref "LED13") (pin "DO") (pinfunction "DO_DO") (pintype "output"))
      (node (ref "LED14") (pin "DI") (pinfunction "DI_DI") (pintype "input"))
    )
    (net (code "49") (name "Net-(LED14-PadDO)") (class "Default")
      (node (ref "LED14") (pin "DO") (pinfunction "DO_DO") (pintype "output"))
      (node (ref "LED15") (pin "DI") (pinfunction "DI_DI") (pintype "input"))
    )
    (net (code "50") (name "Net-(LED15-PadDO)") (class "Default")
      (node (ref "LED15") (pin "DO") (pinfunction "DO_DO") (pintype "output"))
      (node (ref "LED16") (pin "DI") (pinfunction "DI_DI") (pintype "input"))
    )
    (net (code "51") (name "Net-(LED16-PadDO)") (class "Default")
      (node (ref "LED16") (pin "DO") (pinfunction "DO_DO") (pintype "output"))
      (node (ref "LED17") (pin "DI") (pinfunction "DI_DI") (pintype "input"))
    )
    (net (code "52") (name "Net-(LED17-PadDO)") (class "Default")
      (node (ref "LED17") (pin "DO") (pinfunction "DO_DO") (pintype "output"))
      (node (ref "LED18") (pin "DI") (pinfunction "DI_DI") (pintype "input"))
    )
    (net (code "53") (name "Net-(LED18-PadDO)") (class "Default")
      (node (ref "LED18") (pin "DO") (pinfunction "DO_DO") (pintype "output"))
      (node (ref "LED19") (pin "DI") (pinfunction "DI_DI") (pintype "input"))
    )
    (net (code "54") (name "Net-(LED19-PadDO)") (class "Default")
      (node (ref "LED19") (pin "DO") (pinfunction "DO_DO") (pintype "output"))
      (node (ref "LED20") (pin "DI") (pinfunction "DI_DI") (pintype "input"))
    )
    (net (code "55") (name "Net-(LED20-PadDO)") (class "Default")
      (node (ref "LED20") (pin "DO") (pinfunction "DO_DO") (pintype "output"))
      (node (ref "LED21") (pin "DI") (pinfunction "DI_DI") (pintype "input"))
    )
    (net (code "56") (name "Net-(LED21-PadDO)") (class "Default")
      (node (ref "LED21") (pin "DO") (pinfunction "DO_DO") (pintype "output"))
      (node (ref "LED22") (pin "DI") (pinfunction "DI_DI") (pintype "input"))
    )
    (net (code "57") (name "Net-(LED22-PadDO)") (class "Default")
      (node (ref "LED22") (pin "DO") (pinfunction "DO_DO") (pintype "output"))
      (node (ref "LED23") (pin "DI") (pinfunction "DI_DI") (pintype "input"))
    )
    (net (code "58") (name "Net-(LED23-PadDO)") (class "Default")
      (node (ref "LED23") (pin "DO") (pinfunction "DO_DO") (pintype "output"))
      (node (ref "LED24") (pin "DI") (pinfunction "DI_DI") (pintype "input"))
    )
    (net (code "59") (name "Net-(LED24-PadDO)") (class "Default")
      (node (ref "LED24") (pin "DO") (pinfunction "DO_DO") (pintype "output"))
      (node (ref "LED25") (pin "DI") (pinfunction "DI_DI") (pintype "input"))
    )
    (net (code "60") (name "Net-(LED25-PadDO)") (class "Default")
      (node (ref "LED25") (pin "DO") (pinfunction "DO_DO") (pintype "output"))
      (node (ref "LED26") (pin "DI") (pinfunction "DI_DI") (pintype "input"))
    )
    (net (code "61") (name "Net-(LED26-PadDO)") (class "Default")
      (node (ref "LED26") (pin "DO") (pinfunction "DO_DO") (pintype "output"))
      (node (ref "LED27") (pin "DI") (pinfunction "DI_DI") (pintype "input"))
    )
    (net (code "62") (name "Net-(LED27-PadDO)") (class "Default")
      (node (ref "LED27") (pin "DO") (pinfunction "DO_DO") (pintype "output"))
      (node (ref "LED28") (pin "DI") (pinfunction "DI_DI") (pintype "input"))
    )
    (net (code "63") (name "Net-(LED28-PadDO)") (class "Default")
      (node (ref "LED28") (pin "DO") (pinfunction "DO_DO") (pintype "output"))
      (node (ref "LED29") (pin "DI") (pinfunction "DI_DI") (pintype "input"))
    )
    (net (code "64") (name "Net-(LED29-PadDO)") (class "Default")
      (node (ref "LED29") (pin "DO") (pinfunction "DO_DO") (pintype "output"))
      (node (ref "LED30") (pin "DI") (pinfunction "DI_DI") (pintype "input"))
    )
    (net (code "65") (name "Net-(LED30-PadDO)") (class "Default")
      (node (ref "LED30") (pin "DO") (pinfunction "DO_DO") (pintype "output"))
      (node (ref "LED31") (pin "DI") (pinfunction "DI_DI") (pintype "input"))
    )
    (net (code "66") (name "Net-(LED31-PadDO)") (class "Default")
      (node (ref "LED31") (pin "DO") (pinfunction "DO_DO") (pintype "output"))
      (node (ref "LED32") (pin "DI") (pinfunction "DI_DI") (pintype "input"))
    )
    (net (code "67") (name "Net-(LED32-PadDO)") (class "Default")
      (node (ref "LED32") (pin "DO") (pinfunction "DO_DO") (pintype "output"))
      (node (ref "LED33") (pin "DI") (pinfunction "DI_DI") (pintype "input"))
    )
    (net (code "68") (name "Net-(LED33-PadDO)") (class "Default")
      (node (ref "LED33") (pin "DO") (pinfunction "DO_DO") (pintype "output"))
      (node (ref "LED34") (pin "DI") (pinfunction "DI_DI") (pintype "input"))
    )
    (net (code "69") (name "Net-(LED34-PadDO)") (class "Default")
      (node (ref "LED34") (pin "DO") (pinfunction "DO_DO") (pintype "output"))
      (node (ref "LED35") (pin "DI") (pinfunction "DI_DI") (pintype "input"))
    )
    (net (code "70") (name "Net-(LED35-PadDO)") (class "Default")
      (node (ref "LED35") (pin "DO") (pinfunction "DO_DO") (pintype "output"))
      (node (ref "LED36") (pin "DI") (pinfunction "DI_DI") (pintype "input"))
    )
    (net (code "71") (name "Net-(LED36-PadDO)") (class "Default")
      (node (ref "LED36") (pin "DO") (pinfunction "DO_DO") (pintype "output"))
      (node (ref "LED37") (pin "DI") (pinfunction "DI_DI") (pintype "input"))
    )
    (net (code "72") (name "Net-(LED37-PadDO)") (class "Default")
      (node (ref "LED37") (pin "DO") (pinfunction "DO_DO") (pintype "output"))
      (node (ref "LED38") (pin "DI") (pinfunction "DI_DI") (pintype "input"))
    )
    (net (code "73") (name "Net-(LED38-PadDO)") (class "Default")
      (node (ref "LED38") (pin "DO") (pinfunction "DO_DO") (pintype "output"))
      (node (ref "LED39") (pin "DI") (pinfunction "DI_DI") (pintype "input"))
    )
    (net (code "74") (name "Net-(LED39-PadDO)") (class "Default")
      (node (ref "LED39") (pin "DO") (pinfunction "DO_DO") (pintype "output"))
      (node (ref "LED40") (pin "DI") (pinfunction "DI_DI") (pintype "input"))
    )
    (net (code "75") (name "Net-(LED40-PadDO)") (class "Default")
      (node (ref "LED40") (pin "DO") (pinfunction "DO_DO") (pintype "output"))
      (node (ref "LED41") (pin "DI") (pinfunction "DI_DI") (pintype "input"))
    )
    (net (code "76") (name "Net-(LED41-PadDO)") (class "Default")
      (node (ref "LED41") (pin "DO") (pinfunction "DO_DO") (pintype "output"))
      (node (ref "LED42") (pin "DI") (pinfunction "DI_DI") (pintype "input"))
    )
    (net (code "77") (name "Net-(LED42-PadDO)") (class "Default")
      (node (ref "LED42") (pin "DO") (pinfunction "DO_DO") (pintype "output"))
      (node (ref "LED43") (pin "DI") (pinfunction "DI_DI") (pintype "input"))
    )
    (net (code "78") (name "Net-(LED43-PadDO)") (class "Default")
      (node (ref "LED43") (pin "DO") (pinfunction "DO_DO") (pintype "output"))
      (node (ref "LED44") (pin "DI") (pinfunction "DI_DI") (pintype "input"))
    )
    (net (code "79") (name "Net-(LED44-PadDO)") (class "Default")
      (node (ref "LED44") (pin "DO") (pinfunction "DO_DO") (pintype "output"))
      (node (ref "LED45") (pin "DI") (pinfunction "DI_DI") (pintype "input"))
    )
    (net (code "80") (name "Net-(LED45-PadDO)") (class "Default")
      (node (ref "LED45") (pin "DO") (pinfunction "DO_DO") (pintype "output"))
      (node (ref "LED46") (pin "DI") (pinfunction "DI_DI") (pintype "input"))
    )
    (net (code "81") (name "Net-(LED46-PadDO)") (class "Default")
      (node (ref "LED46") (pin "DO") (pinfunction "DO_DO") (pintype "output"))
      (node (ref "LED47") (pin "DI") (pinfunction "DI_DI") (pintype "input"))
    )
    (net (code "82") (name "Net-(LED47-PadDO)") (class "Default")
      (node (ref "LED47") (pin "DO") (pinfunction "DO_DO") (pintype "output"))
      (node (ref "LED48") (pin "DI") (pinfunction "DI_DI") (pintype "input"))
    )
    (net (code "83") (name "Net-(LED48-PadDO)") (class "Default")
      (node (ref "LED48") (pin "DO") (pinfunction "DO_DO") (pintype "output"))
      (node (ref "LED49") (pin "DI") (pinfunction "DI_DI") (pintype "input"))
    )
    (net (code "84") (name "Net-(LED49-PadDO)") (class "Default")
      (node (ref "LED49") (pin "DO") (pinfunction "DO_DO") (pintype "output"))
      (node (ref "LED50") (pin "DI") (pinfunction "DI_DI") (pintype "input"))
    )
    (net (code "85") (name "Net-(LED50-PadDO)") (class "Default")
      (node (ref "LED50") (pin "DO") (pinfunction "DO_DO") (pintype "output"))
      (node (ref "LED51") (pin "DI") (pinfunction "DI_DI") (pintype "input"))
    )
    (net (code "86") (name "Net-(LED51-PadDO)") (class "Default")
      (node (ref "LED51") (pin "DO") (pinfunction "DO_DO") (pintype "output"))
      (node (ref "LED52") (pin "DI") (pinfunction "DI_DI") (pintype "input"))
    )
    (net (code "87") (name "Net-(LED52-PadDO)") (class "Default")
      (node (ref "LED52") (pin "DO") (pinfunction "DO_DO") (pintype "output"))
      (node (ref "LED53") (pin "DI") (pinfunction "DI_DI") (pintype "input"))
    )
    (net (code "88") (name "Net-(LED53-PadDO)") (class "Default")
      (node (ref "LED53") (pin "DO") (pinfunction "DO_DO") (pintype "output"))
      (node (ref "LED54") (pin "DI") (pinfunction "DI_DI") (pintype "input"))
    )
    (net (code "89") (name "Net-(LED54-PadDO)") (class "Default")
      (node (ref "LED54") (pin "DO") (pinfunction "DO_DO") (pintype "output"))
      (node (ref "LED55") (pin "DI") (pinfunction "DI_DI") (pintype "input"))
    )
    (net (code "90") (name "Net-(LED55-PadDO)") (class "Default")
      (node (ref "LED55") (pin "DO") (pinfunction "DO_DO") (pintype "output"))
      (node (ref "LED56") (pin "DI") (pinfunction "DI_DI") (pintype "input"))
    )
    (net (code "91") (name "Net-(LED56-PadDO)") (class "Default")
      (node (ref "LED56") (pin "DO") (pinfunction "DO_DO") (pintype "output"))
      (node (ref "LED57") (pin "DI") (pinfunction "DI_DI") (pintype "input"))
    )
    (net (code "92") (name "Net-(LED57-PadDO)") (class "Default")
      (node (ref "LED57") (pin "DO") (pinfunction "DO_DO") (pintype "output"))
      (node (ref "LED58") (pin "DI") (pinfunction "DI_DI") (pintype "input"))
    )
    (net (code "93") (name "Net-(LED58-PadDO)") (class "Default")
      (node (ref "LED58") (pin "DO") (pinfunction "DO_DO") (pintype "output"))
      (node (ref "LED59") (pin "DI") (pinfunction "DI_DI") (pintype "input"))
    )
    (net (code "94") (name "Net-(LED59-PadDO)") (class "Default")
      (node (ref "LED59") (pin "DO") (pinfunction "DO_DO") (pintype "output"))
      (node (ref "LED60") (pin "DI") (pinfunction "DI_DI") (pintype "input"))
    )
  )
)
